# v1_2-no-regulator.net
KiCad netlist of a schematic drawn in EAGLE
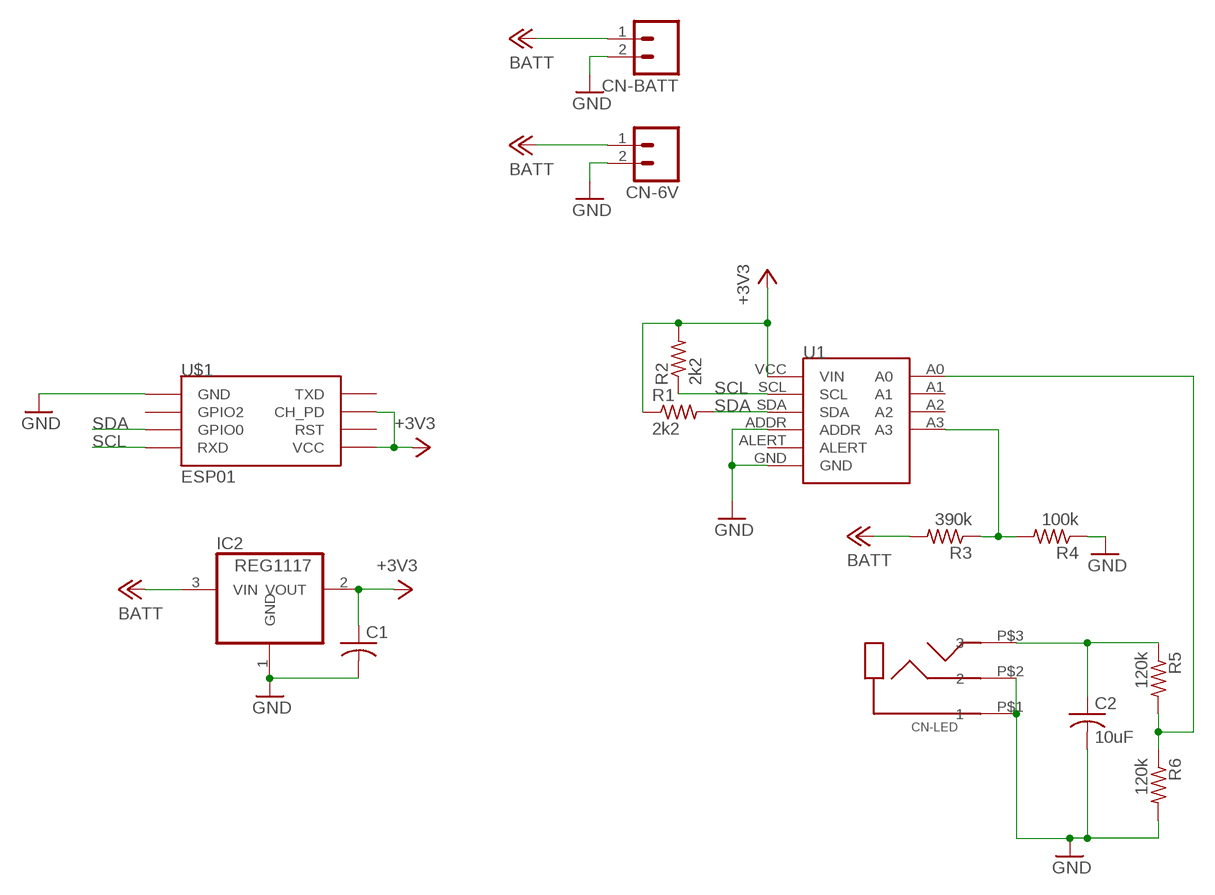
[diagram p0: schematic, sheet 1]

(export (version "E")
  (design (tool "Eeschema 10.0.6"))
  (components
    (comp (ref "C1")
      (value "C-USC1210")
      (footprint "eagle-import:C1210")
      (libsource (lib "eagle-import") (part "C-USC1210"))
    )
    (comp (ref "C2")
      (value "10uF")
      (footprint "eagle-import:C0805K")
      (libsource (lib "eagle-import") (part "C-USC0805K"))
    )
    (comp (ref "CN-6V")
      (value "M02")
      (footprint "eagle-import:02P")
      (libsource (lib "eagle-import") (part "M02"))
    )
    (comp (ref "CN-BATT")
      (value "M02")
      (footprint "eagle-import:02P")
      (libsource (lib "eagle-import") (part "M02"))
    )
    (comp (ref "CN-LED")
      (value "PJ-320B")
      (footprint "eagle-import:PJ-320B")
      (libsource (lib "eagle-import") (part "PJ-320B"))
    )
    (comp (ref "IC2")
      (value "REG1117")
      (footprint "eagle-import:SOT223")
      (libsource (lib "eagle-import") (part "REG1117"))
    )
    (comp (ref "R1")
      (value "2k2")
      (footprint "eagle-import:R0603")
      (libsource (lib "eagle-import") (part "R-US_R0603"))
    )
    (comp (ref "R2")
      (value "2k2")
      (footprint "eagle-import:R0603")
      (libsource (lib "eagle-import") (part "R-US_R0603"))
    )
    (comp (ref "R3")
      (value "390k")
      (footprint "eagle-import:R0603")
      (libsource (lib "eagle-import") (part "R-US_R0603"))
    )
    (comp (ref "R4")
      (value "100k")
      (footprint "eagle-import:R0603")
      (libsource (lib "eagle-import") (part "R-US_R0603"))
    )
    (comp (ref "R5")
      (value "120k")
      (footprint "eagle-import:R0603")
      (libsource (lib "eagle-import") (part "R-US_R0603"))
    )
    (comp (ref "R6")
      (value "120k")
      (footprint "eagle-import:R0603")
      (libsource (lib "eagle-import") (part "R-US_R0603"))
    )
    (comp (ref "U$1")
      (value "ESP01")
      (footprint "eagle-import:ESP01")
      (libsource (lib "eagle-import") (part "ESP01"))
    )
    (comp (ref "U1")
      (value "GY-ADS1115THM")
      (footprint "eagle-import:GY-ADS1115-THM")
      (libsource (lib "eagle-import") (part "GY-ADS1115THM"))
    )
  )
  (nets
    (net (code "1") (name "+3V3") (class "Default")
      (node (ref "C1") (pin "1") (pinfunction "1_1") (pintype "passive"))
      (node (ref "IC2") (pin "2") (pinfunction "VOUT_2") (pintype "output"))
      (node (ref "R1") (pin "1") (pinfunction "1_1") (pintype "passive"))
      (node (ref "R2") (pin "2") (pinfunction "2_2") (pintype "passive"))
      (node (ref "U$1") (pin "CH_PD") (pinfunction "CH_PD_CH_PD") (pintype "bidirectional"))
      (node (ref "U$1") (pin "VCC") (pinfunction "VCC_VCC") (pintype "bidirectional"))
      (node (ref "U1") (pin "VCC") (pinfunction "VIN_VCC") (pintype "bidirectional"))
    )
    (net (code "2") (name "/SCL") (class "Default")
      (node (ref "R2") (pin "1") (pinfunction "1_1") (pintype "passive"))
      (node (ref "U$1") (pin "RX") (pinfunction "RXD_RX") (pintype "bidirectional"))
      (node (ref "U1") (pin "SCL") (pinfunction "SCL_SCL") (pintype "bidirectional"))
    )
    (net (code "3") (name "/SDA") (class "Default")
      (node (ref "R1") (pin "2") (pinfunction "2_2") (pintype "passive"))
      (node (ref "U$1") (pin "GPIO0") (pinfunction "GPIO0_GPIO0") (pintype "bidirectional"))
      (node (ref "U1") (pin "SDA") (pinfunction "SDA_SDA") (pintype "bidirectional"))
    )
    (net (code "4") (name "BATT") (class "Default")
      (node (ref "CN-6V") (pin "1") (pinfunction "1_1") (pintype "passive"))
      (node (ref "CN-BATT") (pin "1") (pinfunction "1_1") (pintype "passive"))
      (node (ref "IC2") (pin "3") (pinfunction "VIN_3") (pintype "input"))
      (node (ref "R3") (pin "2") (pinfunction "2_2") (pintype "passive"))
    )
    (net (code "5") (name "GND") (class "Default")
      (node (ref "C1") (pin "2") (pinfunction "2_2") (pintype "passive"))
      (node (ref "C2") (pin "2") (pinfunction "2_2") (pintype "passive"))
      (node (ref "CN-6V") (pin "2") (pinfunction "2_2") (pintype "passive"))
      (node (ref "CN-BATT") (pin "2") (pinfunction "2_2") (pintype "passive"))
      (node (ref "CN-LED") (pin "P$1") (pinfunction "1_P$1") (pintype "bidirectional"))
      (node (ref "CN-LED") (pin "P$2") (pinfunction "2_P$2") (pintype "bidirectional"))
      (node (ref "IC2") (pin "1") (pinfunction "GND_1") (pintype "power_in"))
      (node (ref "R4") (pin "1") (pinfunction "1_1") (pintype "passive"))
      (node (ref "R6") (pin "2") (pinfunction "2_2") (pintype "passive"))
      (node (ref "U$1") (pin "GND") (pinfunction "GND_GND") (pintype "bidirectional"))
      (node (ref "U1") (pin "ADDR") (pinfunction "ADDR_ADDR") (pintype "bidirectional"))
      (node (ref "U1") (pin "GND") (pinfunction "GND_GND") (pintype "bidirectional"))
    )
    (net (code "6") (name "Net-(CN-LED-3)") (class "Default")
      (node (ref "C2") (pin "1") (pinfunction "1_1") (pintype "passive"))
      (node (ref "CN-LED") (pin "P$3") (pinfunction "3_P$3") (pintype "bidirectional"))
      (node (ref "R5") (pin "1") (pinfunction "1_1") (pintype "passive"))
    )
    (net (code "7") (name "Net-(R3-Pad1)") (class "Default")
      (node (ref "R3") (pin "1") (pinfunction "1_1") (pintype "passive"))
      (node (ref "R4") (pin "2") (pinfunction "2_2") (pintype "passive"))
      (node (ref "U1") (pin "A3") (pinfunction "A3_A3") (pintype "bidirectional"))
    )
    (net (code "8") (name "Net-(R5-Pad2)") (class "Default")
      (node (ref "R5") (pin "2") (pinfunction "2_2") (pintype "passive"))
      (node (ref "R6") (pin "1") (pinfunction "1_1") (pintype "passive"))
      (node (ref "U1") (pin "A0") (pinfunction "A0_A0") (pintype "bidirectional"))
    )
    (net (code "9") (name "unconnected-(U$1-PadGPIO2)") (class "Default")
      (node (ref "U$1") (pin "GPIO2") (pinfunction "GPIO2_GPIO2") (pintype "bidirectional"))
    )
    (net (code "10") (name "unconnected-(U$1-PadRST)") (class "Default")
      (node (ref "U$1") (pin "RST") (pinfunction "RST_RST") (pintype "bidirectional"))
    )
    (net (code "11") (name "unconnected-(U$1-TXD-PadTX)") (class "Default")
      (node (ref "U$1") (pin "TX") (pinfunction "TXD_TX") (pintype "bidirectional"))
    )
    (net (code "12") (name "unconnected-(U1-PadA1)") (class "Default")
      (node (ref "U1") (pin "A1") (pinfunction "A1_A1") (pintype "bidirectional"))
    )
    (net (code "13") (name "unconnected-(U1-PadA2)") (class "Default")
      (node (ref "U1") (pin "A2") (pinfunction "A2_A2") (pintype "bidirectional"))
    )
    (net (code "14") (name "unconnected-(U1-PadALERT)") (class "Default")
      (node (ref "U1") (pin "ALERT") (pinfunction "ALERT_ALERT") (pintype "bidirectional"))
    )
  )
)
